# My_GuitarPedal_Schematic.net
KiCad netlist of a schematic drawn in EAGLE
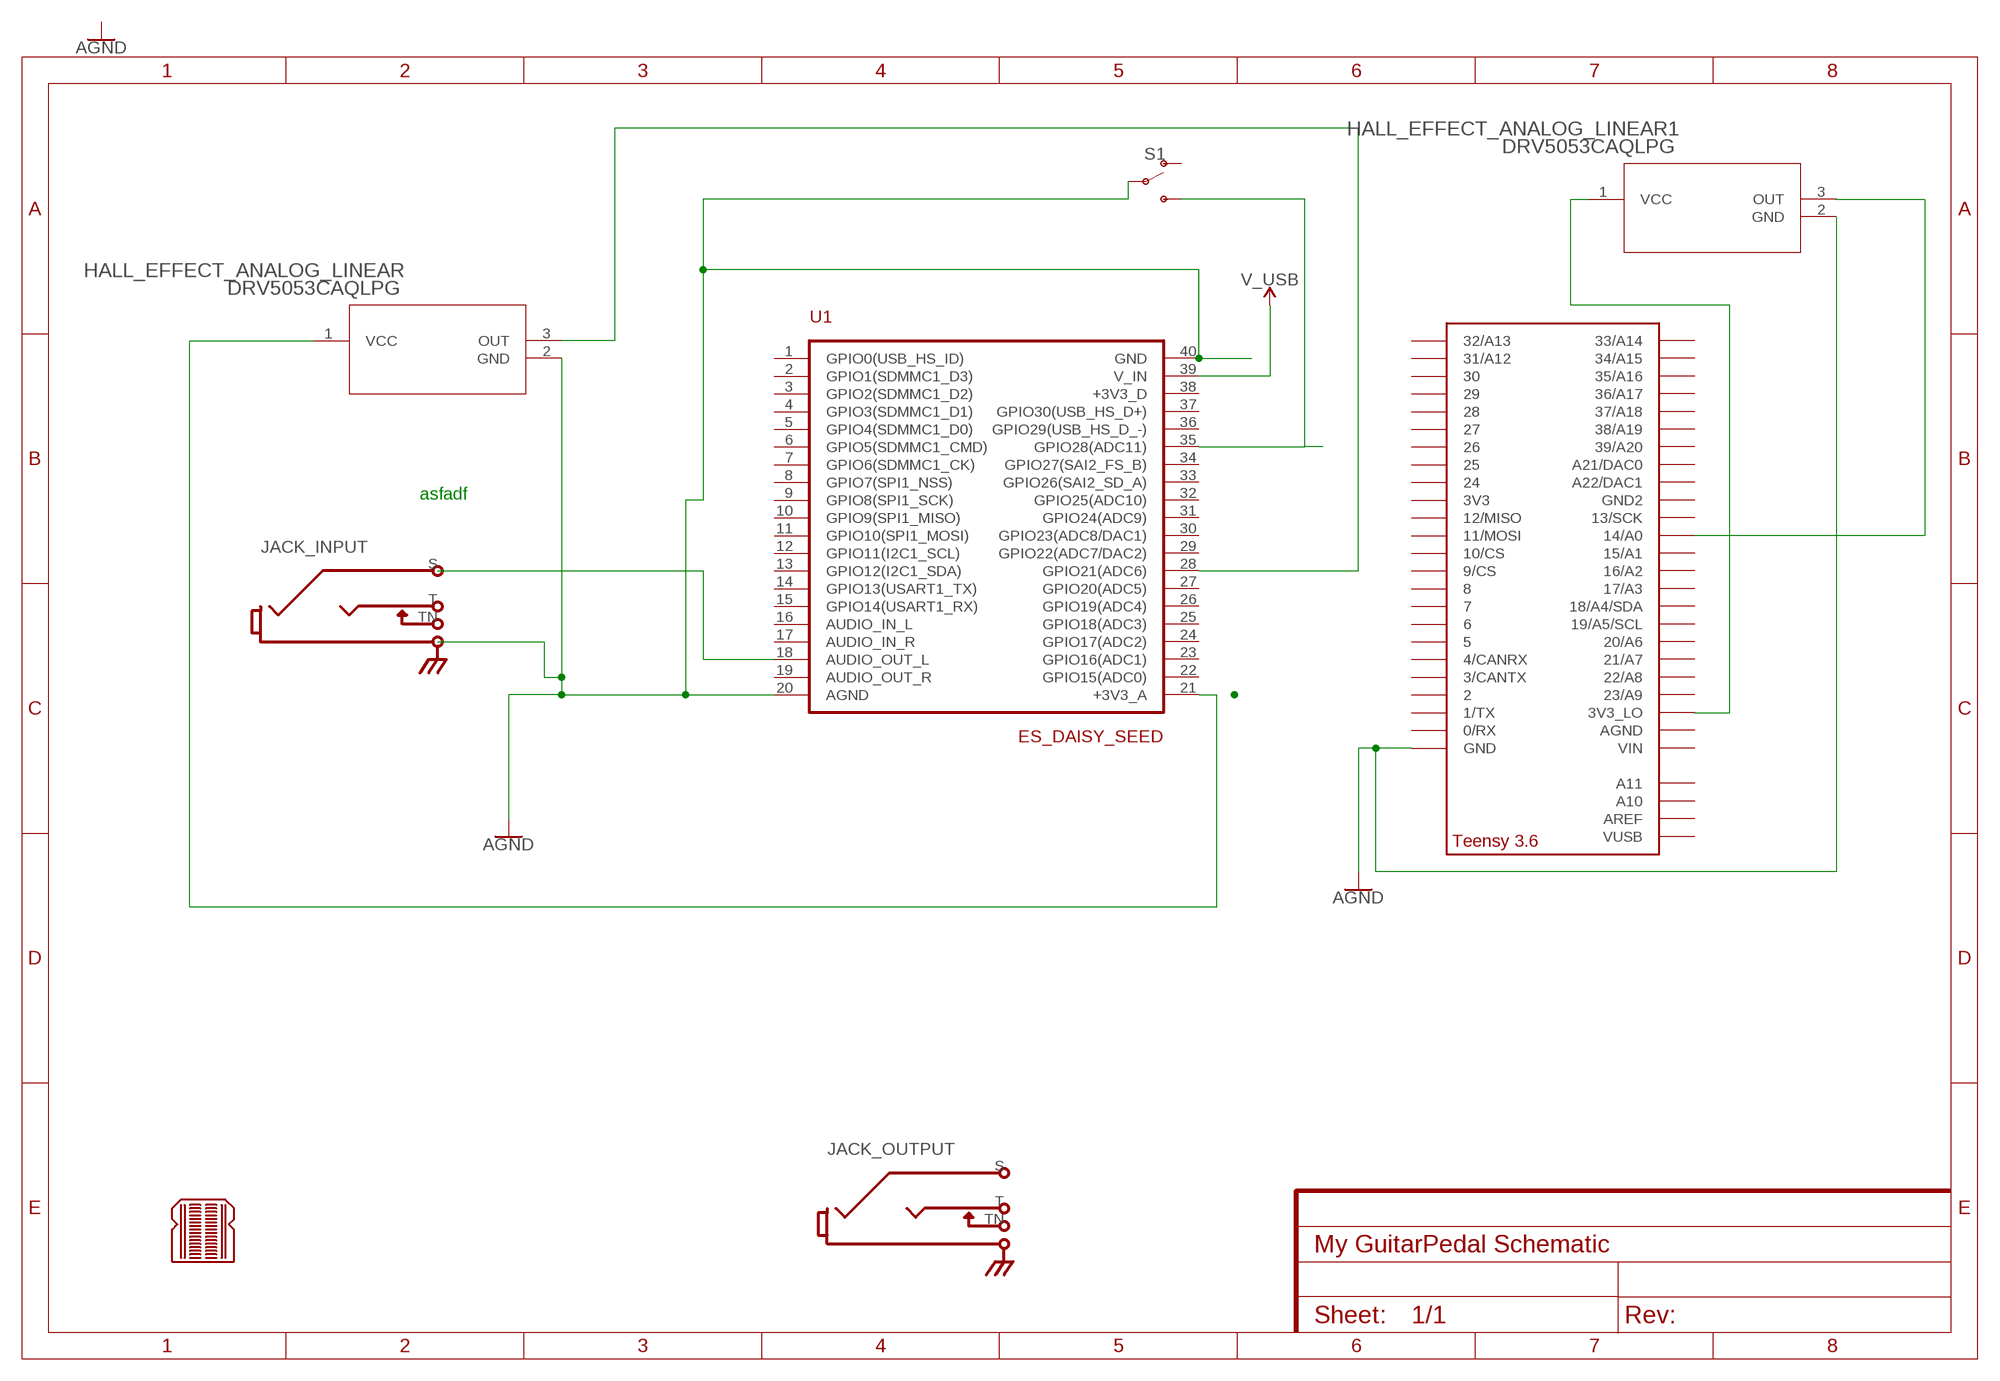
[diagram p0: schematic, sheet 1, part 1 of 2]
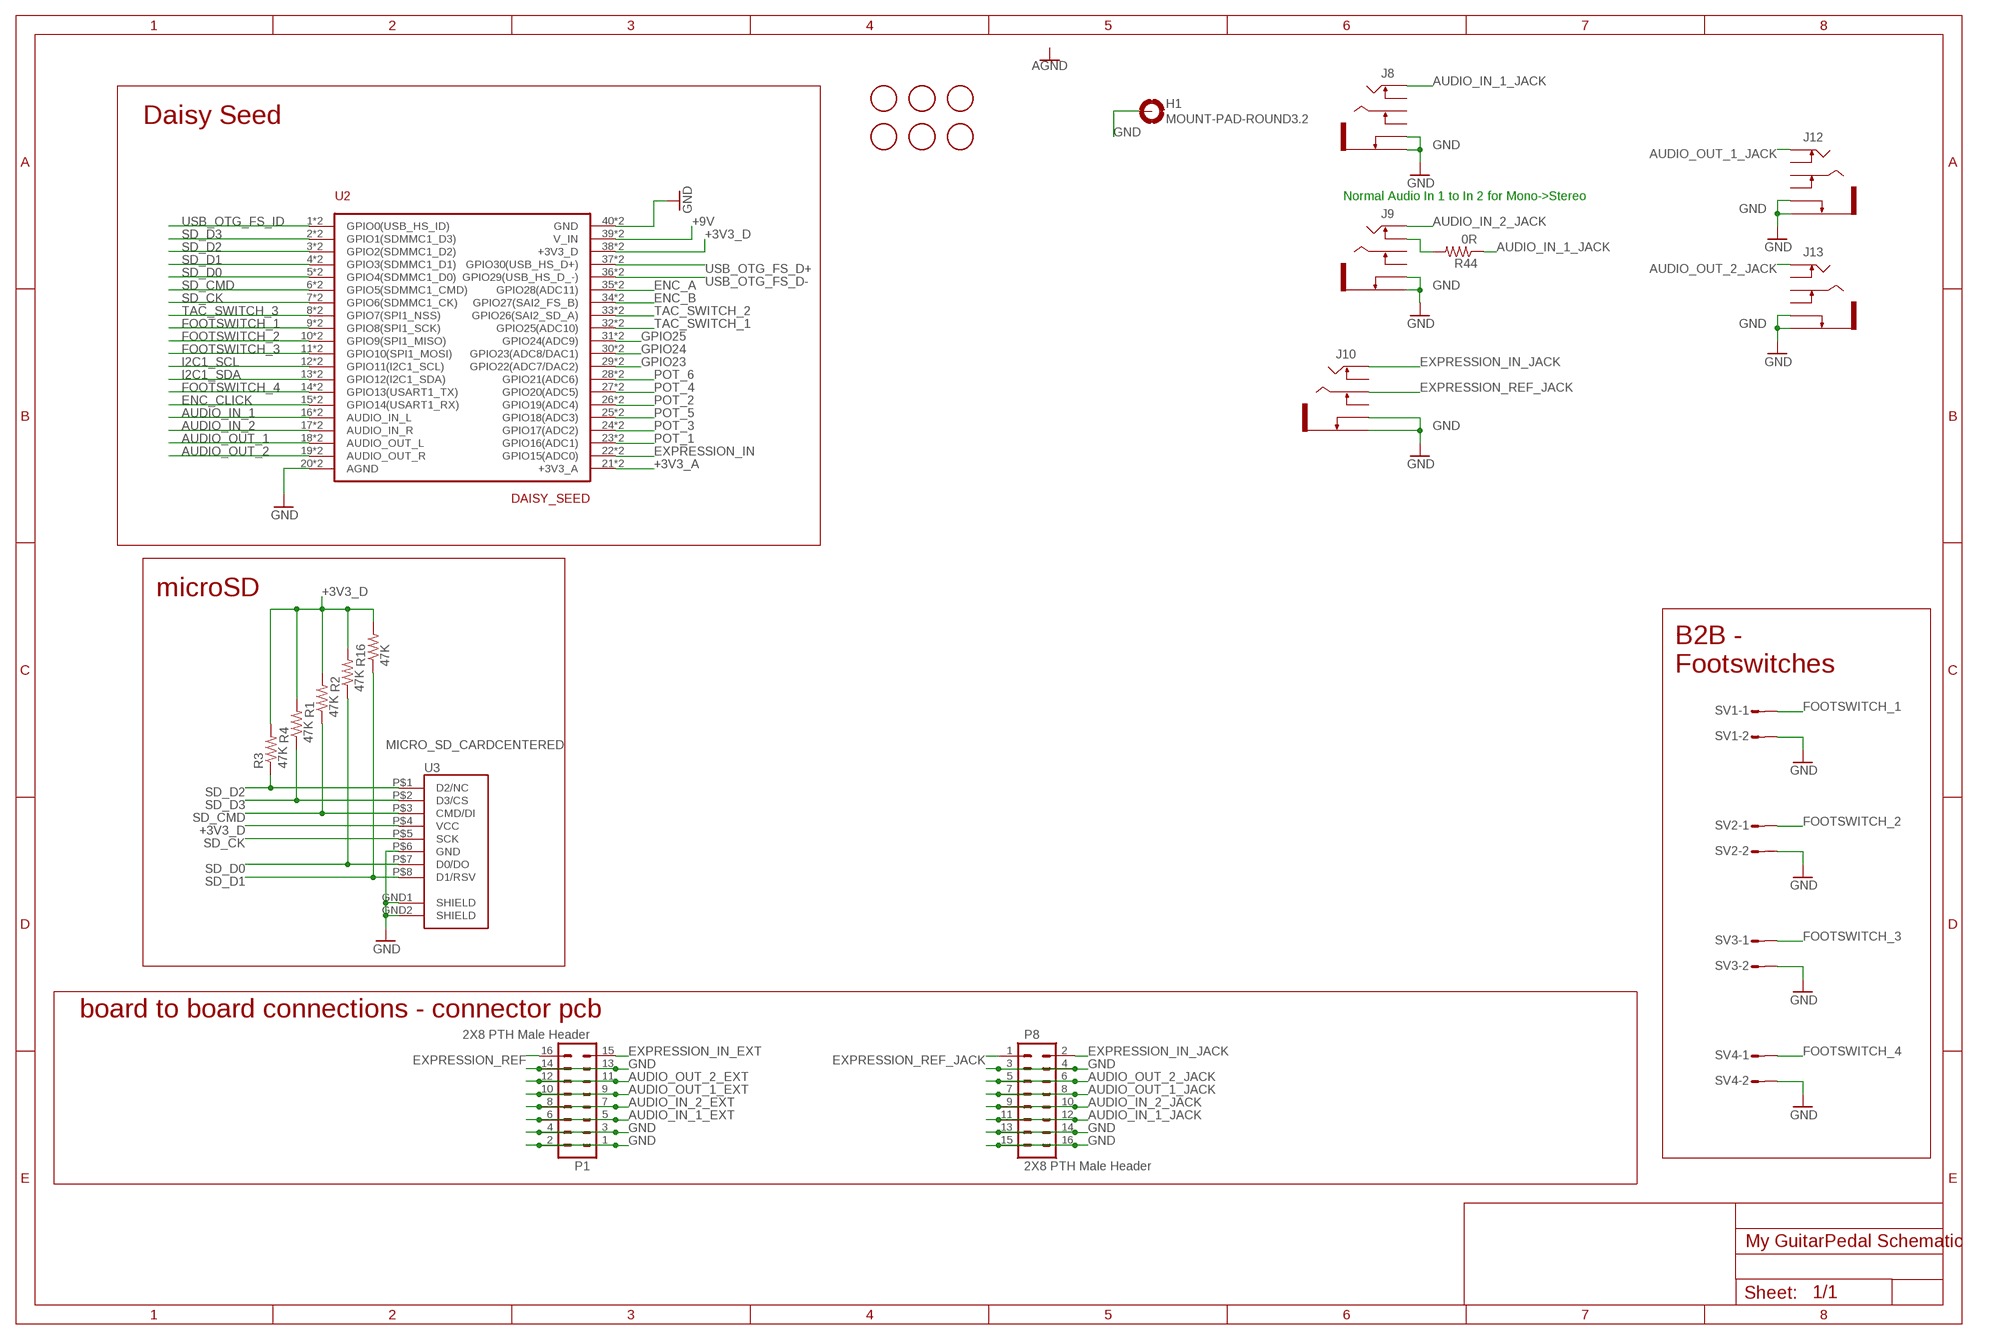
[diagram p1: schematic, sheet 1, part 2 of 2]

(export (version "E")
  (design (tool "Eeschema 10.0.6"))
  (components
    (comp (ref "FD1")
      (value "FIDUCIAL")
      (footprint "eagle-import:FIDUCIAL_1MM")
      (libsource (lib "eagle-import") (part "FIDUCIAL"))
    )
    (comp (ref "FD2")
      (value "FIDUCIAL")
      (footprint "eagle-import:FIDUCIAL_1MM")
      (libsource (lib "eagle-import") (part "FIDUCIAL"))
    )
    (comp (ref "FD3")
      (value "FIDUCIAL")
      (footprint "eagle-import:FIDUCIAL_1MM")
      (libsource (lib "eagle-import") (part "FIDUCIAL"))
    )
    (comp (ref "FD4")
      (value "FIDUCIAL")
      (footprint "eagle-import:FIDUCIAL_1MM")
      (libsource (lib "eagle-import") (part "FIDUCIAL"))
    )
    (comp (ref "FD5")
      (value "FIDUCIAL")
      (footprint "eagle-import:FIDUCIAL_1MM")
      (libsource (lib "eagle-import") (part "FIDUCIAL"))
    )
    (comp (ref "FD6")
      (value "FIDUCIAL")
      (footprint "eagle-import:FIDUCIAL_1MM")
      (libsource (lib "eagle-import") (part "FIDUCIAL"))
    )
    (comp (ref "H1")
      (value "MOUNT-PAD-ROUND3.2")
      (footprint "eagle-import:3,2-PAD")
      (libsource (lib "eagle-import") (part "MOUNT-PAD-ROUND3.2"))
    )
    (comp (ref "HALL_EFFECT_ANALOG_LINEAR")
      (value "DRV5053CAQLPG")
      (footprint "eagle-import:LPG3_TEX")
      (fields (field (name "COPYRIGHT") "Copyright (C) 2022 Ultra Librarian. All rights reserved."))
      (libsource (lib "eagle-import") (part "DRV5053CAQLPG"))
    )
    (comp (ref "HALL_EFFECT_ANALOG_LINEAR1")
      (value "DRV5053CAQLPG")
      (footprint "eagle-import:LPG3_TEX")
      (fields (field (name "COPYRIGHT") "Copyright (C) 2022 Ultra Librarian. All rights reserved."))
      (libsource (lib "eagle-import") (part "DRV5053CAQLPG"))
    )
    (comp (ref "J8")
      (value "JACK_TRS_SWITCHING_WQP-PJ6110")
      (footprint "eagle-import:WQP-PJ6110")
      (libsource (lib "eagle-import") (part "JACK_TRS_SWITCHING_WQP-PJ6110"))
    )
    (comp (ref "J9")
      (value "JACK_TRS_SWITCHING_WQP-PJ6110")
      (footprint "eagle-import:WQP-PJ6110")
      (libsource (lib "eagle-import") (part "JACK_TRS_SWITCHING_WQP-PJ6110"))
    )
    (comp (ref "J10")
      (value "JACK_TRS_SWITCHING_WQP-PJ6110")
      (footprint "eagle-import:WQP-PJ6110")
      (libsource (lib "eagle-import") (part "JACK_TRS_SWITCHING_WQP-PJ6110"))
    )
    (comp (ref "J12")
      (value "JACK_TRS_SWITCHING_WQP-PJ6110")
      (footprint "eagle-import:WQP-PJ6110")
      (libsource (lib "eagle-import") (part "JACK_TRS_SWITCHING_WQP-PJ6110"))
    )
    (comp (ref "J13")
      (value "JACK_TRS_SWITCHING_WQP-PJ6110")
      (footprint "eagle-import:WQP-PJ6110")
      (libsource (lib "eagle-import") (part "JACK_TRS_SWITCHING_WQP-PJ6110"))
    )
    (comp (ref "JACK_INPUT")
      (value "MONOSW1GND")
      (footprint "eagle-import:NEUTRIK-NRJ4HM-1")
      (libsource (lib "eagle-import") (part "MONOSW1GND"))
    )
    (comp (ref "JACK_OUTPUT")
      (value "MONOSW1GND")
      (footprint "eagle-import:NEUTRIK-NRJ4HM-1")
      (libsource (lib "eagle-import") (part "MONOSW1GND"))
    )
    (comp (ref "LOGO1")
      (value "BREADBOARD_PATTERN")
      (footprint "eagle-import:BREADBOARD_SPACING")
      (libsource (lib "eagle-import") (part "BREADBOARD_PATTERN"))
    )
    (comp (ref "P1")
      (value "2X8 PTH Male Header")
      (footprint "eagle-import:2X8_SMD")
      (fields (field (name "LABEL") "TO JACK PCB"))
      (libsource (lib "eagle-import") (part "M08X2?"))
    )
    (comp (ref "P8")
      (value "2X8 PTH Male Header")
      (footprint "eagle-import:2X8_LOCK")
      (libsource (lib "eagle-import") (part "M08X2?_LOCK_SILK"))
    )
    (comp (ref "R1")
      (value "47K")
      (footprint "eagle-import:R0603")
      (libsource (lib "eagle-import") (part "R-US_R0603"))
    )
    (comp (ref "R2")
      (value "47K")
      (footprint "eagle-import:R0603")
      (libsource (lib "eagle-import") (part "R-US_R0603"))
    )
    (comp (ref "R3")
      (value "47K")
      (footprint "eagle-import:R0603")
      (libsource (lib "eagle-import") (part "R-US_R0603"))
    )
    (comp (ref "R4")
      (value "47K")
      (footprint "eagle-import:R0603")
      (libsource (lib "eagle-import") (part "R-US_R0603"))
    )
    (comp (ref "R16")
      (value "47K")
      (footprint "eagle-import:R0603")
      (libsource (lib "eagle-import") (part "R-US_R0603"))
    )
    (comp (ref "R44")
      (value "0R")
      (footprint "eagle-import:R0603")
      (libsource (lib "eagle-import") (part "R-US_R0603"))
    )
    (comp (ref "S1")
      (value "SWITCH-SPDT-SMD-RIGHT-ANGLE")
      (footprint "eagle-import:SWITCH_SPST_SMD_A")
      (libsource (lib "eagle-import") (part "SWITCH-SPDT-SMD-RIGHT-ANGLE"))
    )
    (comp (ref "SV1")
      (value "S02P")
      (footprint "eagle-import:S02P")
      (libsource (lib "eagle-import") (part "S02P"))
    )
    (comp (ref "SV2")
      (value "S02P")
      (footprint "eagle-import:S02P")
      (libsource (lib "eagle-import") (part "S02P"))
    )
    (comp (ref "SV3")
      (value "S02P")
      (footprint "eagle-import:S02P")
      (libsource (lib "eagle-import") (part "S02P"))
    )
    (comp (ref "SV4")
      (value "S02P")
      (footprint "eagle-import:S02P")
      (libsource (lib "eagle-import") (part "S02P"))
    )
    (comp (ref "U$2")
      (value "TEENSY_3.5/3.6_BASIC")
      (footprint "eagle-import:TEENSY_3.5_3.6_BASIC")
      (libsource (lib "eagle-import") (part "TEENSY_3.5/3.6_BASIC"))
    )
    (comp (ref "U1")
      (value "ES_DAISY_SEED")
      (footprint "eagle-import:ES_DAISY_SEED")
      (libsource (lib "eagle-import") (part "ES_DAISY_SEED"))
    )
    (comp (ref "U2")
      (value "DAISY_SEED")
      (footprint "eagle-import:ES_DAISY_SEED_DOUBLE")
      (libsource (lib "eagle-import") (part "ES_DAISY_SEED_REV4_DOUBLE"))
    )
    (comp (ref "U3")
      (value "MICRO_SD_CARDCENTERED")
      (footprint "eagle-import:VERT_MICROSD_CENTERED")
      (libsource (lib "eagle-import") (part "MICRO_SD_CARDCENTERED"))
    )
  )
  (nets
    (net (code "1") (name "/+3V3_A") (class "Default")
      (node (ref "U2") (pin "21") (pinfunction "+3V3_A_21") (pintype "bidirectional"))
      (node (ref "U2") (pin "B21") (pinfunction "+3V3_A_B21") (pintype "bidirectional"))
    )
    (net (code "2") (name "/+3V3_D") (class "Default")
      (node (ref "R1") (pin "2") (pinfunction "2_2") (pintype "passive"))
      (node (ref "R16") (pin "2") (pinfunction "2_2") (pintype "passive"))
      (node (ref "R2") (pin "2") (pinfunction "2_2") (pintype "passive"))
      (node (ref "R3") (pin "2") (pinfunction "2_2") (pintype "passive"))
      (node (ref "R4") (pin "2") (pinfunction "2_2") (pintype "passive"))
      (node (ref "U2") (pin "38") (pinfunction "+3V3_D_38") (pintype "bidirectional"))
      (node (ref "U2") (pin "B38") (pinfunction "+3V3_D_B38") (pintype "bidirectional"))
      (node (ref "U3") (pin "P$4") (pinfunction "VCC_P$4") (pintype "bidirectional"))
    )
    (net (code "3") (name "/+9V") (class "Default")
      (node (ref "U2") (pin "39") (pinfunction "V_IN_39") (pintype "bidirectional"))
      (node (ref "U2") (pin "B39") (pinfunction "V_IN_B39") (pintype "bidirectional"))
    )
    (net (code "4") (name "/AUDIO_IN_1") (class "Default")
      (node (ref "U2") (pin "16") (pinfunction "AUDIO_IN_L_16") (pintype "bidirectional"))
      (node (ref "U2") (pin "B16") (pinfunction "AUDIO_IN_L_B16") (pintype "bidirectional"))
    )
    (net (code "5") (name "/AUDIO_IN_1_EXT") (class "Default")
      (node (ref "P1") (pin "5") (pinfunction "5_5") (pintype "passive"))
      (node (ref "P1") (pin "6") (pinfunction "6_6") (pintype "passive"))
    )
    (net (code "6") (name "/AUDIO_IN_1_JACK") (class "Default")
      (node (ref "J8") (pin "2") (pinfunction "TIP_2") (pintype "passive"))
      (node (ref "P8") (pin "11") (pinfunction "11_11") (pintype "passive"))
      (node (ref "P8") (pin "12") (pinfunction "12_12") (pintype "passive"))
      (node (ref "R44") (pin "1") (pinfunction "1_1") (pintype "passive"))
    )
    (net (code "7") (name "/AUDIO_IN_2") (class "Default")
      (node (ref "U2") (pin "17") (pinfunction "AUDIO_IN_R_17") (pintype "bidirectional"))
      (node (ref "U2") (pin "B17") (pinfunction "AUDIO_IN_R_B17") (pintype "bidirectional"))
    )
    (net (code "8") (name "/AUDIO_IN_2_EXT") (class "Default")
      (node (ref "P1") (pin "7") (pinfunction "7_7") (pintype "passive"))
      (node (ref "P1") (pin "8") (pinfunction "8_8") (pintype "passive"))
    )
    (net (code "9") (name "/AUDIO_IN_2_JACK") (class "Default")
      (node (ref "J9") (pin "2") (pinfunction "TIP_2") (pintype "passive"))
      (node (ref "P8") (pin "10") (pinfunction "10_10") (pintype "passive"))
      (node (ref "P8") (pin "9") (pinfunction "9_9") (pintype "passive"))
    )
    (net (code "10") (name "/AUDIO_OUT_1") (class "Default")
      (node (ref "U2") (pin "18") (pinfunction "AUDIO_OUT_L_18") (pintype "bidirectional"))
      (node (ref "U2") (pin "B18") (pinfunction "AUDIO_OUT_L_B18") (pintype "bidirectional"))
    )
    (net (code "11") (name "/AUDIO_OUT_1_EXT") (class "Default")
      (node (ref "P1") (pin "10") (pinfunction "10_10") (pintype "passive"))
      (node (ref "P1") (pin "9") (pinfunction "9_9") (pintype "passive"))
    )
    (net (code "12") (name "/AUDIO_OUT_1_JACK") (class "Default")
      (node (ref "J12") (pin "2") (pinfunction "TIP_2") (pintype "passive"))
      (node (ref "P8") (pin "7") (pinfunction "7_7") (pintype "passive"))
      (node (ref "P8") (pin "8") (pinfunction "8_8") (pintype "passive"))
    )
    (net (code "13") (name "/AUDIO_OUT_2") (class "Default")
      (node (ref "U2") (pin "19") (pinfunction "AUDIO_OUT_R_19") (pintype "bidirectional"))
      (node (ref "U2") (pin "B19") (pinfunction "AUDIO_OUT_R_B19") (pintype "bidirectional"))
    )
    (net (code "14") (name "/AUDIO_OUT_2_EXT") (class "Default")
      (node (ref "P1") (pin "11") (pinfunction "11_11") (pintype "passive"))
      (node (ref "P1") (pin "12") (pinfunction "12_12") (pintype "passive"))
    )
    (net (code "15") (name "/AUDIO_OUT_2_JACK") (class "Default")
      (node (ref "J13") (pin "2") (pinfunction "TIP_2") (pintype "passive"))
      (node (ref "P8") (pin "5") (pinfunction "5_5") (pintype "passive"))
      (node (ref "P8") (pin "6") (pinfunction "6_6") (pintype "passive"))
    )
    (net (code "16") (name "/ENC_A") (class "Default")
      (node (ref "U2") (pin "35") (pinfunction "GPIO28(ADC11)_35") (pintype "bidirectional"))
      (node (ref "U2") (pin "B35") (pinfunction "GPIO28(ADC11)_B35") (pintype "bidirectional"))
    )
    (net (code "17") (name "/ENC_B") (class "Default")
      (node (ref "U2") (pin "34") (pinfunction "GPIO27(SAI2_FS_B)_34") (pintype "bidirectional"))
      (node (ref "U2") (pin "B34") (pinfunction "GPIO27(SAI2_FS_B)_B34") (pintype "bidirectional"))
    )
    (net (code "18") (name "/ENC_CLICK") (class "Default")
      (node (ref "U2") (pin "15") (pinfunction "GPIO14(USART1_RX)_15") (pintype "bidirectional"))
      (node (ref "U2") (pin "B15") (pinfunction "GPIO14(USART1_RX)_B15") (pintype "bidirectional"))
    )
    (net (code "19") (name "/EXPRESSION_IN") (class "Default")
      (node (ref "U2") (pin "22") (pinfunction "GPIO15(ADC0)_22") (pintype "bidirectional"))
      (node (ref "U2") (pin "B22") (pinfunction "GPIO15(ADC0)_B22") (pintype "bidirectional"))
    )
    (net (code "20") (name "/EXPRESSION_IN_EXT") (class "Default")
      (node (ref "P1") (pin "15") (pinfunction "15_15") (pintype "passive"))
    )
    (net (code "21") (name "/EXPRESSION_IN_JACK") (class "Default")
      (node (ref "J10") (pin "2") (pinfunction "TIP_2") (pintype "passive"))
      (node (ref "P8") (pin "2") (pinfunction "2_2") (pintype "passive"))
    )
    (net (code "22") (name "/EXPRESSION_REF") (class "Default")
      (node (ref "P1") (pin "16") (pinfunction "16_16") (pintype "passive"))
    )
    (net (code "23") (name "/EXPRESSION_REF_JACK") (class "Default")
      (node (ref "J10") (pin "3") (pinfunction "RING_3") (pintype "passive"))
      (node (ref "P8") (pin "1") (pinfunction "1_1") (pintype "passive"))
    )
    (net (code "24") (name "/FOOTSWITCH_1") (class "Default")
      (node (ref "SV1") (pin "1") (pinfunction "S_1") (pintype "passive"))
      (node (ref "U2") (pin "9") (pinfunction "GPIO8(SPI1_SCK)_9") (pintype "bidirectional"))
      (node (ref "U2") (pin "B9") (pinfunction "GPIO8(SPI1_SCK)_B9") (pintype "bidirectional"))
    )
    (net (code "25") (name "/FOOTSWITCH_2") (class "Default")
      (node (ref "SV2") (pin "1") (pinfunction "S_1") (pintype "passive"))
      (node (ref "U2") (pin "10") (pinfunction "GPIO9(SPI1_MISO)_10") (pintype "bidirectional"))
      (node (ref "U2") (pin "B10") (pinfunction "GPIO9(SPI1_MISO)_B10") (pintype "bidirectional"))
    )
    (net (code "26") (name "/FOOTSWITCH_3") (class "Default")
      (node (ref "SV3") (pin "1") (pinfunction "S_1") (pintype "passive"))
      (node (ref "U2") (pin "11") (pinfunction "GPIO10(SPI1_MOSI)_11") (pintype "bidirectional"))
      (node (ref "U2") (pin "B11") (pinfunction "GPIO10(SPI1_MOSI)_B11") (pintype "bidirectional"))
    )
    (net (code "27") (name "/FOOTSWITCH_4") (class "Default")
      (node (ref "SV4") (pin "1") (pinfunction "S_1") (pintype "passive"))
      (node (ref "U2") (pin "14") (pinfunction "GPIO13(USART1_TX)_14") (pintype "bidirectional"))
      (node (ref "U2") (pin "B14") (pinfunction "GPIO13(USART1_TX)_B14") (pintype "bidirectional"))
    )
    (net (code "28") (name "/GPIO23") (class "Default")
      (node (ref "U2") (pin "29") (pinfunction "GPIO22(ADC7/DAC2)_29") (pintype "bidirectional"))
      (node (ref "U2") (pin "B29") (pinfunction "GPIO22(ADC7/DAC2)_B29") (pintype "bidirectional"))
    )
    (net (code "29") (name "/GPIO24") (class "Default")
      (node (ref "U2") (pin "30") (pinfunction "GPIO23(ADC8/DAC1)_30") (pintype "bidirectional"))
      (node (ref "U2") (pin "B30") (pinfunction "GPIO23(ADC8/DAC1)_B30") (pintype "bidirectional"))
    )
    (net (code "30") (name "/GPIO25") (class "Default")
      (node (ref "U2") (pin "31") (pinfunction "GPIO24(ADC9)_31") (pintype "bidirectional"))
      (node (ref "U2") (pin "B31") (pinfunction "GPIO24(ADC9)_B31") (pintype "bidirectional"))
    )
    (net (code "31") (name "/I2C1_SCL") (class "Default")
      (node (ref "U2") (pin "12") (pinfunction "GPIO11(I2C1_SCL)_12") (pintype "bidirectional"))
      (node (ref "U2") (pin "B12") (pinfunction "GPIO11(I2C1_SCL)_B12") (pintype "bidirectional"))
    )
    (net (code "32") (name "/I2C1_SDA") (class "Default")
      (node (ref "U2") (pin "13") (pinfunction "GPIO12(I2C1_SDA)_13") (pintype "bidirectional"))
      (node (ref "U2") (pin "B13") (pinfunction "GPIO12(I2C1_SDA)_B13") (pintype "bidirectional"))
    )
    (net (code "33") (name "/POT_1") (class "Default")
      (node (ref "U2") (pin "23") (pinfunction "GPIO16(ADC1)_23") (pintype "bidirectional"))
      (node (ref "U2") (pin "B23") (pinfunction "GPIO16(ADC1)_B23") (pintype "bidirectional"))
    )
    (net (code "34") (name "/POT_2") (class "Default")
      (node (ref "U2") (pin "26") (pinfunction "GPIO19(ADC4)_26") (pintype "bidirectional"))
      (node (ref "U2") (pin "B26") (pinfunction "GPIO19(ADC4)_B26") (pintype "bidirectional"))
    )
    (net (code "35") (name "/POT_3") (class "Default")
      (node (ref "U2") (pin "24") (pinfunction "GPIO17(ADC2)_24") (pintype "bidirectional"))
      (node (ref "U2") (pin "B24") (pinfunction "GPIO17(ADC2)_B24") (pintype "bidirectional"))
    )
    (net (code "36") (name "/POT_4") (class "Default")
      (node (ref "U2") (pin "27") (pinfunction "GPIO20(ADC5)_27") (pintype "bidirectional"))
      (node (ref "U2") (pin "B27") (pinfunction "GPIO20(ADC5)_B27") (pintype "bidirectional"))
    )
    (net (code "37") (name "/POT_5") (class "Default")
      (node (ref "U2") (pin "25") (pinfunction "GPIO18(ADC3)_25") (pintype "bidirectional"))
      (node (ref "U2") (pin "B25") (pinfunction "GPIO18(ADC3)_B25") (pintype "bidirectional"))
    )
    (net (code "38") (name "/POT_6") (class "Default")
      (node (ref "U2") (pin "28") (pinfunction "GPIO21(ADC6)_28") (pintype "bidirectional"))
      (node (ref "U2") (pin "B28") (pinfunction "GPIO21(ADC6)_B28") (pintype "bidirectional"))
    )
    (net (code "39") (name "/SD_CK") (class "Default")
      (node (ref "U2") (pin "7") (pinfunction "GPIO6(SDMMC1_CK)_7") (pintype "bidirectional"))
      (node (ref "U2") (pin "B7") (pinfunction "GPIO6(SDMMC1_CK)_B7") (pintype "bidirectional"))
      (node (ref "U3") (pin "P$5") (pinfunction "SCK_P$5") (pintype "bidirectional"))
    )
    (net (code "40") (name "/SD_CMD") (class "Default")
      (node (ref "R1") (pin "1") (pinfunction "1_1") (pintype "passive"))
      (node (ref "U2") (pin "6") (pinfunction "GPIO5(SDMMC1_CMD)_6") (pintype "bidirectional"))
      (node (ref "U2") (pin "B6") (pinfunction "GPIO5(SDMMC1_CMD)_B6") (pintype "bidirectional"))
      (node (ref "U3") (pin "P$3") (pinfunction "CMD/DI_P$3") (pintype "bidirectional"))
    )
    (net (code "41") (name "/SD_D0") (class "Default")
      (node (ref "R2") (pin "1") (pinfunction "1_1") (pintype "passive"))
      (node (ref "U2") (pin "5") (pinfunction "GPIO4(SDMMC1_D0)_5") (pintype "bidirectional"))
      (node (ref "U2") (pin "B5") (pinfunction "GPIO4(SDMMC1_D0)_B5") (pintype "bidirectional"))
      (node (ref "U3") (pin "P$7") (pinfunction "D0/DO_P$7") (pintype "bidirectional"))
    )
    (net (code "42") (name "/SD_D1") (class "Default")
      (node (ref "R16") (pin "1") (pinfunction "1_1") (pintype "passive"))
      (node (ref "U2") (pin "4") (pinfunction "GPIO3(SDMMC1_D1)_4") (pintype "bidirectional"))
      (node (ref "U2") (pin "B4") (pinfunction "GPIO3(SDMMC1_D1)_B4") (pintype "bidirectional"))
      (node (ref "U3") (pin "P$8") (pinfunction "D1/RSV_P$8") (pintype "bidirectional"))
    )
    (net (code "43") (name "/SD_D2") (class "Default")
      (node (ref "R3") (pin "1") (pinfunction "1_1") (pintype "passive"))
      (node (ref "U2") (pin "3") (pinfunction "GPIO2(SDMMC1_D2)_3") (pintype "bidirectional"))
      (node (ref "U2") (pin "B3") (pinfunction "GPIO2(SDMMC1_D2)_B3") (pintype "bidirectional"))
      (node (ref "U3") (pin "P$1") (pinfunction "D2/NC_P$1") (pintype "bidirectional"))
    )
    (net (code "44") (name "/SD_D3") (class "Default")
      (node (ref "R4") (pin "1") (pinfunction "1_1") (pintype "passive"))
      (node (ref "U2") (pin "2") (pinfunction "GPIO1(SDMMC1_D3)_2") (pintype "bidirectional"))
      (node (ref "U2") (pin "B2") (pinfunction "GPIO1(SDMMC1_D3)_B2") (pintype "bidirectional"))
      (node (ref "U3") (pin "P$2") (pinfunction "D3/CS_P$2") (pintype "bidirectional"))
    )
    (net (code "45") (name "/TAC_SWITCH_1") (class "Default")
      (node (ref "U2") (pin "32") (pinfunction "GPIO25(ADC10)_32") (pintype "bidirectional"))
      (node (ref "U2") (pin "B32") (pinfunction "GPIO25(ADC10)_B32") (pintype "bidirectional"))
    )
    (net (code "46") (name "/TAC_SWITCH_2") (class "Default")
      (node (ref "U2") (pin "33") (pinfunction "GPIO26(SAI2_SD_A)_33") (pintype "bidirectional"))
      (node (ref "U2") (pin "B33") (pinfunction "GPIO26(SAI2_SD_A)_B33") (pintype "bidirectional"))
    )
    (net (code "47") (name "/TAC_SWITCH_3") (class "Default")
      (node (ref "U2") (pin "8") (pinfunction "GPIO7(SPI1_NSS)_8") (pintype "bidirectional"))
      (node (ref "U2") (pin "B8") (pinfunction "GPIO7(SPI1_NSS)_B8") (pintype "bidirectional"))
    )
    (net (code "48") (name "/USB_OTG_FS_D+") (class "Default")
      (node (ref "U2") (pin "37") (pinfunction "GPIO30(USB_HS_D+)_37") (pintype "bidirectional"))
      (node (ref "U2") (pin "B37") (pinfunction "GPIO30(USB_HS_D+)_B37") (pintype "bidirectional"))
    )
    (net (code "49") (name "/USB_OTG_FS_D-") (class "Default")
      (node (ref "U2") (pin "36") (pinfunction "GPIO29(USB_HS_D_-)_36") (pintype "bidirectional"))
      (node (ref "U2") (pin "B36") (pinfunction "GPIO29(USB_HS_D_-)_B36") (pintype "bidirectional"))
    )
    (net (code "50") (name "/USB_OTG_FS_ID") (class "Default")
      (node (ref "U2") (pin "1") (pinfunction "GPIO0(USB_HS_ID)_1") (pintype "bidirectional"))
      (node (ref "U2") (pin "B1") (pinfunction "GPIO0(USB_HS_ID)_B1") (pintype "bidirectional"))
    )
    (net (code "51") (name "AGND") (class "Default")
      (node (ref "HALL_EFFECT_ANALOG_LINEAR") (pin "2") (pinfunction "GND_2") (pintype "power_in"))
      (node (ref "HALL_EFFECT_ANALOG_LINEAR1") (pin "2") (pinfunction "GND_2") (pintype "power_in"))
      (node (ref "S1") (pin "2") (pinfunction "P_2") (pintype "passive"))
      (node (ref "U$2") (pin "GND") (pinfunction "GND_GND") (pintype "bidirectional"))
      (node (ref "U1") (pin "20") (pinfunction "AGND_20") (pintype "bidirectional"))
      (node (ref "U1") (pin "40") (pinfunction "GND_40") (pintype "bidirectional"))
    )
    (net (code "52") (name "GND") (class "Default")
      (node (ref "H1") (pin "B3,2") (pinfunction "MOUNT_B3,2") (pintype "passive"))
      (node (ref "J10") (pin "1") (pinfunction "SLEEVE_1") (pintype "passive"))
      (node (ref "J10") (pin "4") (pinfunction "SLEEVE_SW_4") (pintype "passive"))
      (node (ref "J12") (pin "1") (pinfunction "SLEEVE_1") (pintype "passive"))
      (node (ref "J12") (pin "4") (pinfunction "SLEEVE_SW_4") (pintype "passive"))
      (node (ref "J13") (pin "1") (pinfunction "SLEEVE_1") (pintype "passive"))
      (node (ref "J13") (pin "4") (pinfunction "SLEEVE_SW_4") (pintype "passive"))
      (node (ref "J8") (pin "1") (pinfunction "SLEEVE_1") (pintype "passive"))
      (node (ref "J8") (pin "4") (pinfunction "SLEEVE_SW_4") (pintype "passive"))
      (node (ref "J9") (pin "1") (pinfunction "SLEEVE_1") (pintype "passive"))
      (node (ref "J9") (pin "4") (pinfunction "SLEEVE_SW_4") (pintype "passive"))
      (node (ref "P1") (pin "1") (pinfunction "1_1") (pintype "passive"))
      (node (ref "P1") (pin "13") (pinfunction "13_13") (pintype "passive"))
      (node (ref "P1") (pin "14") (pinfunction "14_14") (pintype "passive"))
      (node (ref "P1") (pin "2") (pinfunction "2_2") (pintype "passive"))
      (node (ref "P1") (pin "3") (pinfunction "3_3") (pintype "passive"))
      (node (ref "P1") (pin "4") (pinfunction "4_4") (pintype "passive"))
      (node (ref "P8") (pin "13") (pinfunction "13_13") (pintype "passive"))
      (node (ref "P8") (pin "14") (pinfunction "14_14") (pintype "passive"))
      (node (ref "P8") (pin "15") (pinfunction "15_15") (pintype "passive"))
      (node (ref "P8") (pin "16") (pinfunction "16_16") (pintype "passive"))
      (node (ref "P8") (pin "3") (pinfunction "3_3") (pintype "passive"))
      (node (ref "P8") (pin "4") (pinfunction "4_4") (pintype "passive"))
      (node (ref "SV1") (pin "2") (pinfunction "S_2") (pintype "passive"))
      (node (ref "SV2") (pin "2") (pinfunction "S_2") (pintype "passive"))
      (node (ref "SV3") (pin "2") (pinfunction "S_2") (pintype "passive"))
      (node (ref "SV4") (pin "2") (pinfunction "S_2") (pintype "passive"))
      (node (ref "U2") (pin "20") (pinfunction "AGND_20") (pintype "bidirectional"))
      (node (ref "U2") (pin "40") (pinfunction "GND_40") (pintype "bidirectional"))
      (node (ref "U2") (pin "B20") (pinfunction "AGND_B20") (pintype "bidirectional"))
      (node (ref "U2") (pin "B40") (pinfunction "GND_B40") (pintype "bidirectional"))
      (node (ref "U3") (pin "GND1") (pinfunction "SHIELD_GND1") (pintype "bidirectional"))
      (node (ref "U3") (pin "GND2") (pinfunction "SHIELD_GND2") (pintype "bidirectional"))
      (node (ref "U3") (pin "P$6") (pinfunction "GND_P$6") (pintype "bidirectional"))
    )
    (net (code "53") (name "Net-(HALL_EFFECT_ANALOG_LINEAR-OUT)") (class "Default")
      (node (ref "HALL_EFFECT_ANALOG_LINEAR") (pin "3") (pinfunction "OUT_3") (pintype "output"))
      (node (ref "U1") (pin "28") (pinfunction "GPIO21(ADC6)_28") (pintype "bidirectional"))
    )
    (net (code "54") (name "Net-(HALL_EFFECT_ANALOG_LINEAR-VCC)") (class "Default")
      (node (ref "HALL_EFFECT_ANALOG_LINEAR") (pin "1") (pinfunction "VCC_1") (pintype "power_in"))
      (node (ref "U1") (pin "21") (pinfunction "+3V3_A_21") (pintype "bidirectional"))
    )
    (net (code "55") (name "Net-(HALL_EFFECT_ANALOG_LINEAR1-OUT)") (class "Default")
      (node (ref "HALL_EFFECT_ANALOG_LINEAR1") (pin "3") (pinfunction "OUT_3") (pintype "output"))
      (node (ref "U$2") (pin "14/A0") (pinfunction "14/A0_14/A0") (pintype "bidirectional"))
    )
    (net (code "56") (name "Net-(HALL_EFFECT_ANALOG_LINEAR1-VCC)") (class "Default")
      (node (ref "HALL_EFFECT_ANALOG_LINEAR1") (pin "1") (pinfunction "VCC_1") (pintype "power_in"))
      (node (ref "U$2") (pin "3V3_LO") (pinfunction "3V3_LO_3V3_LO") (pintype "bidirectional"))
    )
    (net (code "57") (name "Net-(J9-TIP_SW)") (class "Default")
      (node (ref "J9") (pin "5") (pinfunction "TIP_SW_5") (pintype "passive"))
      (node (ref "R44") (pin "2") (pinfunction "2_2") (pintype "passive"))
    )
    (net (code "58") (name "Net-(S1-S)") (class "Default")
      (node (ref "S1") (pin "3") (pinfunction "S_3") (pintype "passive"))
      (node (ref "U1") (pin "35") (pinfunction "GPIO28(ADC11)_35") (pintype "bidirectional"))
    )
    (net (code "59") (name "Net-(U1-AUDIO_OUT_L)") (class "Default")
      (node (ref "JACK_INPUT") (pin "S") (pinfunction "S_S") (pintype "passive"))
      (node (ref "U1") (pin "18") (pinfunction "AUDIO_OUT_L_18") (pintype "bidirectional"))
    )
    (net (code "60") (name "V_USB") (class "Default")
      (node (ref "U1") (pin "39") (pinfunction "V_IN_39") (pintype "bidirectional"))
    )
    (net (code "61") (name "unconnected-(J8-RING-Pad3)") (class "Default")
      (node (ref "J8") (pin "3") (pinfunction "RING_3") (pintype "passive"))
    )
    (net (code "62") (name "unconnected-(J8-RING_SW-Pad6)") (class "Default")
      (node (ref "J8") (pin "6") (pinfunction "RING_SW_6") (pintype "passive"))
    )
    (net (code "63") (name "unconnected-(J8-TIP_SW-Pad5)") (class "Default")
      (node (ref "J8") (pin "5") (pinfunction "TIP_SW_5") (pintype "passive"))
    )
    (net (code "64") (name "unconnected-(J9-RING-Pad3)") (class "Default")
      (node (ref "J9") (pin "3") (pinfunction "RING_3") (pintype "passive"))
    )
    (net (code "65") (name "unconnected-(J9-RING_SW-Pad6)") (class "Default")
      (node (ref "J9") (pin "6") (pinfunction "RING_SW_6") (pintype "passive"))
    )
    (net (code "66") (name "unconnected-(J10-RING_SW-Pad6)") (class "Default")
      (node (ref "J10") (pin "6") (pinfunction "RING_SW_6") (pintype "passive"))
    )
    (net (code "67") (name "unconnected-(J10-TIP_SW-Pad5)") (class "Default")
      (node (ref "J10") (pin "5") (pinfunction "TIP_SW_5") (pintype "passive"))
    )
    (net (code "68") (name "unconnected-(J12-RING-Pad3)") (class "Default")
      (node (ref "J12") (pin "3") (pinfunction "RING_3") (pintype "passive"))
    )
    (net (code "69") (name "unconnected-(J12-RING_SW-Pad6)") (class "Default")
      (node (ref "J12") (pin "6") (pinfunction "RING_SW_6") (pintype "passive"))
    )
    (net (code "70") (name "unconnected-(J12-TIP_SW-Pad5)") (class "Default")
      (node (ref "J12") (pin "5") (pinfunction "TIP_SW_5") (pintype "passive"))
    )
    (net (code "71") (name "unconnected-(J13-RING-Pad3)") (class "Default")
      (node (ref "J13") (pin "3") (pinfunction "RING_3") (pintype "passive"))
    )
    (net (code "72") (name "unconnected-(J13-RING_SW-Pad6)") (class "Default")
      (node (ref "J13") (pin "6") (pinfunction "RING_SW_6") (pintype "passive"))
    )
    (net (code "73") (name "unconnected-(J13-TIP_SW-Pad5)") (class "Default")
      (node (ref "J13") (pin "5") (pinfunction "TIP_SW_5") (pintype "passive"))
    )
    (net (code "74") (name "unconnected-(JACK_INPUT-PadT)") (class "Default")
      (node (ref "JACK_INPUT") (pin "T") (pinfunction "T_T") (pintype "passive"))
    )
    (net (code "75") (name "unconnected-(JACK_INPUT-PadTN)") (class "Default")
      (node (ref "JACK_INPUT") (pin "TN") (pinfunction "TN_TN") (pintype "passive"))
    )
    (net (code "76") (name "unconnected-(JACK_OUTPUT-PadS)") (class "Default")
      (node (ref "JACK_OUTPUT") (pin "S") (pinfunction "S_S") (pintype "passive"))
    )
    (net (code "77") (name "unconnected-(JACK_OUTPUT-PadT)") (class "Default")
      (node (ref "JACK_OUTPUT") (pin "T") (pinfunction "T_T") (pintype "passive"))
    )
    (net (code "78") (name "unconnected-(JACK_OUTPUT-PadTN)") (class "Default")
      (node (ref "JACK_OUTPUT") (pin "TN") (pinfunction "TN_TN") (pintype "passive"))
    )
    (net (code "79") (name "unconnected-(S1-O-Pad1)") (class "Default")
      (node (ref "S1") (pin "1") (pinfunction "O_1") (pintype "passive"))
    )
    (net (code "80") (name "unconnected-(U$2-A21{slash}DAC0-Pad21{slash}DAC0)") (class "Default")
      (node (ref "U$2") (pin "21/DAC0") (pinfunction "A21/DAC0_21/DAC0") (pintype "bidirectional"))
    )
    (net (code "81") (name "unconnected-(U$2-Pad0{slash}RX)") (class "Default")
      (node (ref "U$2") (pin "0/RX") (pinfunction "0/RX_0/RX") (pintype "bidirectional"))
    )
    (net (code "82") (name "unconnected-(U$2-Pad1{slash}TX)") (class "Default")
      (node (ref "U$2") (pin "1/TX") (pinfunction "1/TX_1/TX") (pintype "bidirectional"))
    )
    (net (code "83") (name "unconnected-(U$2-Pad2)") (class "Default")
      (node (ref "U$2") (pin "2") (pinfunction "2_2") (pintype "bidirectional"))
    )
    (net (code "84") (name "unconnected-(U$2-Pad3V3)") (class "Default")
      (node (ref "U$2") (pin "3V3") (pinfunction "3V3_3V3") (pintype "bidirectional"))
    )
    (net (code "85") (name "unconnected-(U$2-Pad3{slash}CANTX)") (class "Default")
      (node (ref "U$2") (pin "3/CANTX") (pinfunction "3/CANTX_3/CANTX") (pintype "bidirectional"))
    )
    (net (code "86") (name "unconnected-(U$2-Pad4{slash}CANRX)") (class "Default")
      (node (ref "U$2") (pin "4/CANRX") (pinfunction "4/CANRX_4/CANRX") (pintype "bidirectional"))
    )
    (net (code "87") (name "unconnected-(U$2-Pad5)") (class "Default")
      (node (ref "U$2") (pin "5") (pinfunction "5_5") (pintype "bidirectional"))
    )
    (net (code "88") (name "unconnected-(U$2-Pad6)") (class "Default")
      (node (ref "U$2") (pin "6") (pinfunction "6_6") (pintype "bidirectional"))
    )
    (net (code "89") (name "unconnected-(U$2-Pad7)") (class "Default")
      (node (ref "U$2") (pin "7") (pinfunction "7_7") (pintype "bidirectional"))
    )
    (net (code "90") (name "unconnected-(U$2-Pad8)") (class "Default")
      (node (ref "U$2") (pin "8") (pinfunction "8_8") (pintype "bidirectional"))
    )
    (net (code "91") (name "unconnected-(U$2-Pad9{slash}CS)") (class "Default")
      (node (ref "U$2") (pin "9/CS") (pinfunction "9/CS_9/CS") (pintype "bidirectional"))
    )
    (net (code "92") (name "unconnected-(U$2-Pad10{slash}CS)") (class "Default")
      (node (ref "U$2") (pin "10/CS") (pinfunction "10/CS_10/CS") (pintype "bidirectional"))
    )
    (net (code "93") (name "unconnected-(U$2-Pad11{slash}MOSI)") (class "Default")
      (node (ref "U$2") (pin "11/MOSI") (pinfunction "11/MOSI_11/MOSI") (pintype "bidirectional"))
    )
    (net (code "94") (name "unconnected-(U$2-Pad12{slash}MISO)") (class "Default")
      (node (ref "U$2") (pin "12/MISO") (pinfunction "12/MISO_12/MISO") (pintype "bidirectional"))
    )
    (net (code "95") (name "unconnected-(U$2-Pad13{slash}SCK)") (class "Default")
      (node (ref "U$2") (pin "13/SCK") (pinfunction "13/SCK_13/SCK") (pintype "bidirectional"))
    )
    (net (code "96") (name "unconnected-(U$2-Pad15{slash}A1)") (class "Default")
      (node (ref "U$2") (pin "15/A1") (pinfunction "15/A1_15/A1") (pintype "bidirectional"))
    )
    (net (code "97") (name "unconnected-(U$2-Pad16{slash}A2)") (class "Default")
      (node (ref "U$2") (pin "16/A2") (pinfunction "16/A2_16/A2") (pintype "bidirectional"))
    )
    (net (code "98") (name "unconnected-(U$2-Pad17{slash}A3)") (class "Default")
      (node (ref "U$2") (pin "17/A3") (pinfunction "17/A3_17/A3") (pintype "bidirectional"))
    )
    (net (code "99") (name "unconnected-(U$2-Pad18{slash}A4{slash}SDA)") (class "Default")
      (node (ref "U$2") (pin "18/A4/SDA") (pinfunction "18/A4/SDA_18/A4/SDA") (pintype "bidirectional"))
    )
    (net (code "100") (name "unconnected-(U$2-Pad19{slash}A5{slash}SCL)") (class "Default")
      (node (ref "U$2") (pin "19/A5/SCL") (pinfunction "19/A5/SCL_19/A5/SCL") (pintype "bidirectional"))
    )
    (net (code "101") (name "unconnected-(U$2-Pad20{slash}A6)") (class "Default")
      (node (ref "U$2") (pin "20/A6") (pinfunction "20/A6_20/A6") (pintype "bidirectional"))
    )
    (net (code "102") (name "unconnected-(U$2-Pad21{slash}A7)") (class "Default")
      (node (ref "U$2") (pin "21/A7") (pinfunction "21/A7_21/A7") (pintype "bidirectional"))
    )
    (net (code "103") (name "unconnected-(U$2-Pad22{slash}A8)") (class "Default")
      (node (ref "U$2") (pin "22/A8") (pinfunction "22/A8_22/A8") (pintype "bidirectional"))
    )
    (net (code "104") (name "unconnected-(U$2-Pad23{slash}A9)") (class "Default")
      (node (ref "U$2") (pin "23/A9") (pinfunction "23/A9_23/A9") (pintype "bidirectional"))
    )
    (net (code "105") (name "unconnected-(U$2-Pad24)") (class "Default")
      (node (ref "U$2") (pin "24") (pinfunction "24_24") (pintype "bidirectional"))
    )
    (net (code "106") (name "unconnected-(U$2-Pad25)") (class "Default")
      (node (ref "U$2") (pin "25") (pinfunction "25_25") (pintype "bidirectional"))
    )
    (net (code "107") (name "unconnected-(U$2-Pad26)") (class "Default")
      (node (ref "U$2") (pin "26") (pinfunction "26_26") (pintype "bidirectional"))
    )
    (net (code "108") (name "unconnected-(U$2-Pad27)") (class "Default")
      (node (ref "U$2") (pin "27") (pinfunction "27_27") (pintype "bidirectional"))
    )
    (net (code "109") (name "unconnected-(U$2-Pad28)") (class "Default")
      (node (ref "U$2") (pin "28") (pinfunction "28_28") (pintype "bidirectional"))
    )
    (net (code "110") (name "unconnected-(U$2-Pad29)") (class "Default")
      (node (ref "U$2") (pin "29") (pinfunction "29_29") (pintype "bidirectional"))
    )
    (net (code "111") (name "unconnected-(U$2-Pad30)") (class "Default")
      (node (ref "U$2") (pin "30") (pinfunction "30_30") (pintype "bidirectional"))
    )
    (net (code "112") (name "unconnected-(U$2-Pad31{slash}A12)") (class "Default")
      (node (ref "U$2") (pin "31/A12") (pinfunction "31/A12_31/A12") (pintype "bidirectional"))
    )
    (net (code "113") (name "unconnected-(U$2-Pad32{slash}A13)") (class "Default")
      (node (ref "U$2") (pin "32/A13") (pinfunction "32/A13_32/A13") (pintype "bidirectional"))
    )
    (net (code "114") (name "unconnected-(U$2-Pad33{slash}A14)") (class "Default")
      (node (ref "U$2") (pin "33/A14") (pinfunction "33/A14_33/A14") (pintype "bidirectional"))
    )
    (net (code "115") (name "unconnected-(U$2-Pad34{slash}A15)") (class "Default")
      (node (ref "U$2") (pin "34/A15") (pinfunction "34/A15_34/A15") (pintype "bidirectional"))
    )
    (net (code "116") (name "unconnected-(U$2-Pad35{slash}A16)") (class "Default")
      (node (ref "U$2") (pin "35/A16") (pinfunction "35/A16_35/A16") (pintype "bidirectional"))
    )
    (net (code "117") (name "unconnected-(U$2-Pad36{slash}A17)") (class "Default")
      (node (ref "U$2") (pin "36/A17") (pinfunction "36/A17_36/A17") (pintype "bidirectional"))
    )
    (net (code "118") (name "unconnected-(U$2-Pad37{slash}A18)") (class "Default")
      (node (ref "U$2") (pin "37/A18") (pinfunction "37/A18_37/A18") (pintype "bidirectional"))
    )
    (net (code "119") (name "unconnected-(U$2-Pad38{slash}A19)") (class "Default")
      (node (ref "U$2") (pin "38/A19") (pinfunction "38/A19_38/A19") (pintype "bidirectional"))
    )
    (net (code "120") (name "unconnected-(U$2-Pad39{slash}A20)") (class "Default")
      (node (ref "U$2") (pin "39/A20") (pinfunction "39/A20_39/A20") (pintype "bidirectional"))
    )
    (net (code "121") (name "unconnected-(U$2-PadA10)") (class "Default")
      (node (ref "U$2") (pin "A10") (pinfunction "A10_A10") (pintype "bidirectional"))
    )
    (net (code "122") (name "unconnected-(U$2-PadA11)") (class "Default")
      (node (ref "U$2") (pin "A11") (pinfunction "A11_A11") (pintype "bidirectional"))
    )
    (net (code "123") (name "unconnected-(U$2-PadA22{slash}DAC1)") (class "Default")
      (node (ref "U$2") (pin "A22/DAC1") (pinfunction "A22/DAC1_A22/DAC1") (pintype "bidirectional"))
    )
    (net (code "124") (name "unconnected-(U$2-PadAGND)") (class "Default")
      (node (ref "U$2") (pin "AGND") (pinfunction "AGND_AGND") (pintype "bidirectional"))
    )
    (net (code "125") (name "unconnected-(U$2-PadAREF)") (class "Default")
      (node (ref "U$2") (pin "AREF") (pinfunction "AREF_AREF") (pintype "bidirectional"))
    )
    (net (code "126") (name "unconnected-(U$2-PadGND2)") (class "Default")
      (node (ref "U$2") (pin "GND2") (pinfunction "GND2_GND2") (pintype "bidirectional"))
    )
    (net (code "127") (name "unconnected-(U$2-PadVIN)") (class "Default")
      (node (ref "U$2") (pin "VIN") (pinfunction "VIN_VIN") (pintype "bidirectional"))
    )
    (net (code "128") (name "unconnected-(U$2-PadVUSB)") (class "Default")
      (node (ref "U$2") (pin "VUSB") (pinfunction "VUSB_VUSB") (pintype "bidirectional"))
    )
    (net (code "129") (name "unconnected-(U1-+3V3_D-Pad38)") (class "Default")
      (node (ref "U1") (pin "38") (pinfunction "+3V3_D_38") (pintype "bidirectional"))
    )
    (net (code "130") (name "unconnected-(U1-AUDIO_IN_L-Pad16)") (class "Default")
      (node (ref "U1") (pin "16") (pinfunction "AUDIO_IN_L_16") (pintype "bidirectional"))
    )
    (net (code "131") (name "unconnected-(U1-AUDIO_IN_R-Pad17)") (class "Default")
      (node (ref "U1") (pin "17") (pinfunction "AUDIO_IN_R_17") (pintype "bidirectional"))
    )
    (net (code "132") (name "unconnected-(U1-AUDIO_OUT_R-Pad19)") (class "Default")
      (node (ref "U1") (pin "19") (pinfunction "AUDIO_OUT_R_19") (pintype "bidirectional"))
    )
    (net (code "133") (name "unconnected-(U1-GPIO0(USB_HS_ID)-Pad1)") (class "Default")
      (node (ref "U1") (pin "1") (pinfunction "GPIO0(USB_HS_ID)_1") (pintype "bidirectional"))
    )
    (net (code "134") (name "unconnected-(U1-GPIO1(SDMMC1_D3)-Pad2)") (class "Default")
      (node (ref "U1") (pin "2") (pinfunction "GPIO1(SDMMC1_D3)_2") (pintype "bidirectional"))
    )
    (net (code "135") (name "unconnected-(U1-GPIO2(SDMMC1_D2)-Pad3)") (class "Default")
      (node (ref "U1") (pin "3") (pinfunction "GPIO2(SDMMC1_D2)_3") (pintype "bidirectional"))
    )
    (net (code "136") (name "unconnected-(U1-GPIO3(SDMMC1_D1)-Pad4)") (class "Default")
      (node (ref "U1") (pin "4") (pinfunction "GPIO3(SDMMC1_D1)_4") (pintype "bidirectional"))
    )
    (net (code "137") (name "unconnected-(U1-GPIO4(SDMMC1_D0)-Pad5)") (class "Default")
      (node (ref "U1") (pin "5") (pinfunction "GPIO4(SDMMC1_D0)_5") (pintype "bidirectional"))
    )
    (net (code "138") (name "unconnected-(U1-GPIO5(SDMMC1_CMD)-Pad6)") (class "Default")
      (node (ref "U1") (pin "6") (pinfunction "GPIO5(SDMMC1_CMD)_6") (pintype "bidirectional"))
    )
    (net (code "139") (name "unconnected-(U1-GPIO6(SDMMC1_CK)-Pad7)") (class "Default")
      (node (ref "U1") (pin "7") (pinfunction "GPIO6(SDMMC1_CK)_7") (pintype "bidirectional"))
    )
    (net (code "140") (name "unconnected-(U1-GPIO7(SPI1_NSS)-Pad8)") (class "Default")
      (node (ref "U1") (pin "8") (pinfunction "GPIO7(SPI1_NSS)_8") (pintype "bidirectional"))
    )
    (net (code "141") (name "unconnected-(U1-GPIO8(SPI1_SCK)-Pad9)") (class "Default")
      (node (ref "U1") (pin "9") (pinfunction "GPIO8(SPI1_SCK)_9") (pintype "bidirectional"))
    )
    (net (code "142") (name "unconnected-(U1-GPIO9(SPI1_MISO)-Pad10)") (class "Default")
      (node (ref "U1") (pin "10") (pinfunction "GPIO9(SPI1_MISO)_10") (pintype "bidirectional"))
    )
    (net (code "143") (name "unconnected-(U1-GPIO10(SPI1_MOSI)-Pad11)") (class "Default")
      (node (ref "U1") (pin "11") (pinfunction "GPIO10(SPI1_MOSI)_11") (pintype "bidirectional"))
    )
    (net (code "144") (name "unconnected-(U1-GPIO11(I2C1_SCL)-Pad12)") (class "Default")
      (node (ref "U1") (pin "12") (pinfunction "GPIO11(I2C1_SCL)_12") (pintype "bidirectional"))
    )
    (net (code "145") (name "unconnected-(U1-GPIO12(I2C1_SDA)-Pad13)") (class "Default")
      (node (ref "U1") (pin "13") (pinfunction "GPIO12(I2C1_SDA)_13") (pintype "bidirectional"))
    )
    (net (code "146") (name "unconnected-(U1-GPIO13(USART1_TX)-Pad14)") (class "Default")
      (node (ref "U1") (pin "14") (pinfunction "GPIO13(USART1_TX)_14") (pintype "bidirectional"))
    )
    (net (code "147") (name "unconnected-(U1-GPIO14(USART1_RX)-Pad15)") (class "Default")
      (node (ref "U1") (pin "15") (pinfunction "GPIO14(USART1_RX)_15") (pintype "bidirectional"))
    )
    (net (code "148") (name "unconnected-(U1-GPIO15(ADC0)-Pad22)") (class "Default")
      (node (ref "U1") (pin "22") (pinfunction "GPIO15(ADC0)_22") (pintype "bidirectional"))
    )
    (net (code "149") (name "unconnected-(U1-GPIO16(ADC1)-Pad23)") (class "Default")
      (node (ref "U1") (pin "23") (pinfunction "GPIO16(ADC1)_23") (pintype "bidirectional"))
    )
    (net (code "150") (name "unconnected-(U1-GPIO17(ADC2)-Pad24)") (class "Default")
      (node (ref "U1") (pin "24") (pinfunction "GPIO17(ADC2)_24") (pintype "bidirectional"))
    )
    (net (code "151") (name "unconnected-(U1-GPIO18(ADC3)-Pad25)") (class "Default")
      (node (ref "U1") (pin "25") (pinfunction "GPIO18(ADC3)_25") (pintype "bidirectional"))
    )
    (net (code "152") (name "unconnected-(U1-GPIO19(ADC4)-Pad26)") (class "Default")
      (node (ref "U1") (pin "26") (pinfunction "GPIO19(ADC4)_26") (pintype "bidirectional"))
    )
    (net (code "153") (name "unconnected-(U1-GPIO20(ADC5)-Pad27)") (class "Default")
      (node (ref "U1") (pin "27") (pinfunction "GPIO20(ADC5)_27") (pintype "bidirectional"))
    )
    (net (code "154") (name "unconnected-(U1-GPIO22(ADC7{slash}DAC2)-Pad29)") (class "Default")
      (node (ref "U1") (pin "29") (pinfunction "GPIO22(ADC7/DAC2)_29") (pintype "bidirectional"))
    )
    (net (code "155") (name "unconnected-(U1-GPIO23(ADC8{slash}DAC1)-Pad30)") (class "Default")
      (node (ref "U1") (pin "30") (pinfunction "GPIO23(ADC8/DAC1)_30") (pintype "bidirectional"))
    )
    (net (code "156") (name "unconnected-(U1-GPIO24(ADC9)-Pad31)") (class "Default")
      (node (ref "U1") (pin "31") (pinfunction "GPIO24(ADC9)_31") (pintype "bidirectional"))
    )
    (net (code "157") (name "unconnected-(U1-GPIO25(ADC10)-Pad32)") (class "Default")
      (node (ref "U1") (pin "32") (pinfunction "GPIO25(ADC10)_32") (pintype "bidirectional"))
    )
    (net (code "158") (name "unconnected-(U1-GPIO26(SAI2_SD_A)-Pad33)") (class "Default")
      (node (ref "U1") (pin "33") (pinfunction "GPIO26(SAI2_SD_A)_33") (pintype "bidirectional"))
    )
    (net (code "159") (name "unconnected-(U1-GPIO27(SAI2_FS_B)-Pad34)") (class "Default")
      (node (ref "U1") (pin "34") (pinfunction "GPIO27(SAI2_FS_B)_34") (pintype "bidirectional"))
    )
    (net (code "160") (name "unconnected-(U1-GPIO29(USB_HS_D_-)-Pad36)") (class "Default")
      (node (ref "U1") (pin "36") (pinfunction "GPIO29(USB_HS_D_-)_36") (pintype "bidirectional"))
    )
    (net (code "161") (name "unconnected-(U1-GPIO30(USB_HS_D+)-Pad37)") (class "Default")
      (node (ref "U1") (pin "37") (pinfunction "GPIO30(USB_HS_D+)_37") (pintype "bidirectional"))
    )
  )
)
